# Frozen_Slimes_v2.net
KiCad netlist of a schematic drawn in EasyEDA
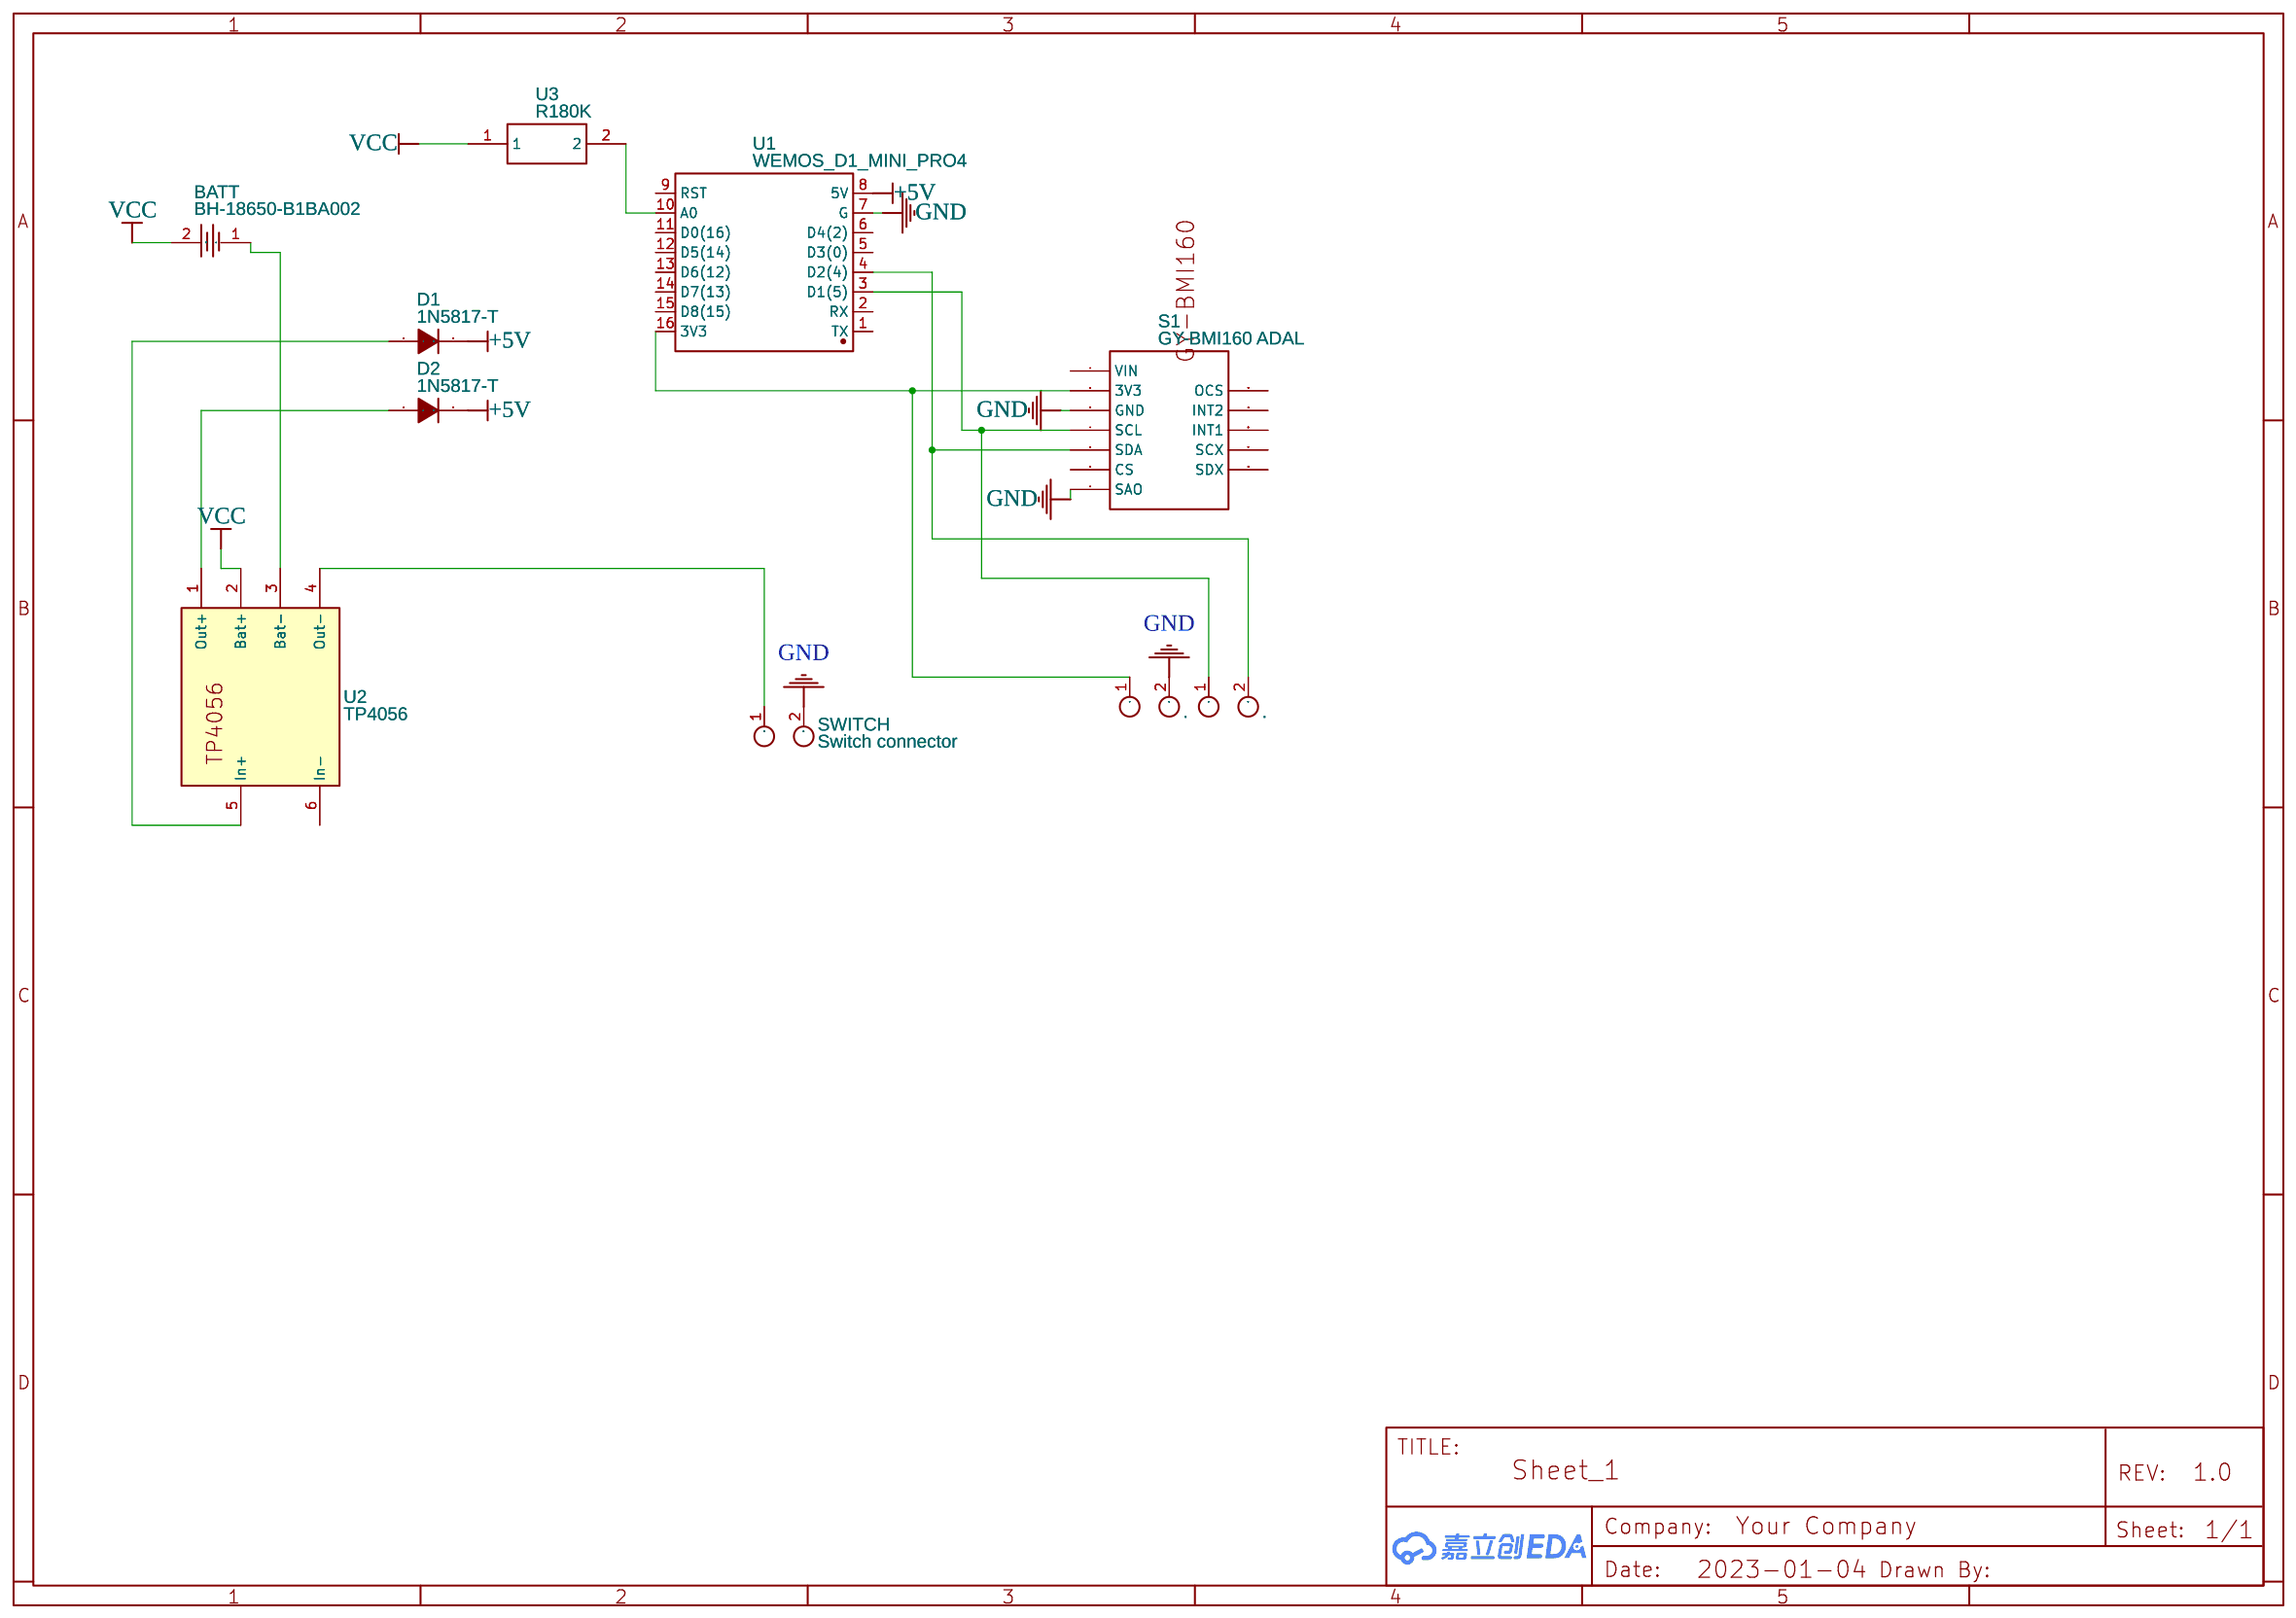
[diagram p0: schematic sheet]

(export (version "E")
  (design (tool "Eeschema 10.0.6"))
  (components
    (comp (ref "BATT")
      (value "BH-18650-B1BA002")
      (fields (field (name "BOM_Supplier Part") "C2988620"))
      (libsource (lib "") (part "BH-18650-B1BA002"))
    )
    (comp (ref "D1")
      (value "1N5817-T")
      (fields (field (name "BOM_Supplier Part") "C507852"))
      (libsource (lib "") (part "1N5817-T"))
    )
    (comp (ref "D2")
      (value "1N5817-T")
      (fields (field (name "BOM_Supplier Part") "C507852"))
      (libsource (lib "") (part "1N5817-T"))
    )
    (comp (ref "S1") (value "GY-BMI160 ADAL") (libsource (lib "") (part "GY-BMI160 ADAL")))
    (comp (ref "SWITCH") (value "Switch connector") (libsource (lib "") (part "2XSOLDER PAD_1")))
    (comp (ref "U1")
      (value "WEMOS_D1_MINI_PRO4")
      (fields
        (field (name "BOM_Manufacturer Part") "Wemos_D1_mini_Pro4")
        (field (name "BOM_Supplier Part") "C2837266")
      )
      (libsource (lib "") (part "WEMOS_D1_MINI_PRO4"))
    )
    (comp (ref "U2") (value "TP4056") (libsource (lib "") (part "TP4056")))
    (comp (ref "U3") (value "R180K") (libsource (lib "") (part "R180K")))
    (comp (ref "U6") (value ".") (libsource (lib "") (part "2XSOLDER PAD")))
    (comp (ref "U7") (value ".") (libsource (lib "") (part "2XSOLDER PAD")))
  )
  (nets
    (net (code "1") (name "+5V") (class "Default")
      (node (ref "D1") (pin "2") (pinfunction "K_2") (pintype "unspecified"))
      (node (ref "D2") (pin "2") (pinfunction "K_2") (pintype "unspecified"))
      (node (ref "U1") (pin "8") (pinfunction "5V_8") (pintype "unspecified"))
    )
    (net (code "2") (name "GND") (class "Default")
      (node (ref "S1") (pin "1") (pinfunction "SAO_1") (pintype "unspecified"))
      (node (ref "S1") (pin "5") (pinfunction "GND_5") (pintype "unspecified"))
      (node (ref "SWITCH") (pin "2") (pinfunction "2_2") (pintype "unspecified"))
      (node (ref "U1") (pin "7") (pinfunction "G_7") (pintype "unspecified"))
      (node (ref "U6") (pin "2") (pinfunction "2_2") (pintype "unspecified"))
    )
    (net (code "3") (name "Net-(D1-A)") (class "Default")
      (node (ref "D1") (pin "1") (pinfunction "A_1") (pintype "unspecified"))
      (node (ref "U2") (pin "5") (pinfunction "In+_5") (pintype "unspecified"))
    )
    (net (code "4") (name "Net-(D2-A)") (class "Default")
      (node (ref "D2") (pin "1") (pinfunction "A_1") (pintype "unspecified"))
      (node (ref "U2") (pin "1") (pinfunction "Out+_1") (pintype "unspecified"))
    )
    (net (code "5") (name "Net-(S1-3V3)") (class "Default")
      (node (ref "S1") (pin "6") (pinfunction "3V3_6") (pintype "unspecified"))
      (node (ref "U1") (pin "16") (pinfunction "3V3_16") (pintype "unspecified"))
      (node (ref "U6") (pin "1") (pinfunction "1_1") (pintype "unspecified"))
    )
    (net (code "6") (name "Net-(S1-SCL)") (class "Default")
      (node (ref "S1") (pin "4") (pinfunction "SCL_4") (pintype "unspecified"))
      (node (ref "U1") (pin "3") (pinfunction "D1(5)_3") (pintype "unspecified"))
      (node (ref "U7") (pin "1") (pinfunction "1_1") (pintype "unspecified"))
    )
    (net (code "7") (name "Net-(S1-SDA)") (class "Default")
      (node (ref "S1") (pin "3") (pinfunction "SDA_3") (pintype "unspecified"))
      (node (ref "U1") (pin "4") (pinfunction "D2(4)_4") (pintype "unspecified"))
      (node (ref "U7") (pin "2") (pinfunction "2_2") (pintype "unspecified"))
    )
    (net (code "8") (name "Net-(U1-A0)") (class "Default")
      (node (ref "U1") (pin "10") (pinfunction "A0_10") (pintype "unspecified"))
      (node (ref "U3") (pin "2") (pinfunction "2_2") (pintype "unspecified"))
    )
    (net (code "9") (name "Net-(U2-Bat-)") (class "Default")
      (node (ref "BATT") (pin "1") (pinfunction "1_1") (pintype "input"))
      (node (ref "U2") (pin "3") (pinfunction "Bat-_3") (pintype "unspecified"))
    )
    (net (code "10") (name "Net-(U2-Out-)") (class "Default")
      (node (ref "SWITCH") (pin "1") (pinfunction "1_1") (pintype "unspecified"))
      (node (ref "U2") (pin "4") (pinfunction "Out-_4") (pintype "unspecified"))
    )
    (net (code "11") (name "VCC") (class "Default")
      (node (ref "BATT") (pin "2") (pinfunction "2_2") (pintype "input"))
      (node (ref "U2") (pin "2") (pinfunction "Bat+_2") (pintype "unspecified"))
      (node (ref "U3") (pin "1") (pinfunction "1_1") (pintype "unspecified"))
    )
    (net (code "12") (name "unconnected-(S1-CS-Pad2)") (class "Default")
      (node (ref "S1") (pin "2") (pinfunction "CS_2") (pintype "unspecified"))
    )
    (net (code "13") (name "unconnected-(S1-INT1-Pad10)") (class "Default")
      (node (ref "S1") (pin "10") (pinfunction "INT1_10") (pintype "unspecified"))
    )
    (net (code "14") (name "unconnected-(S1-INT2-Pad9)") (class "Default")
      (node (ref "S1") (pin "9") (pinfunction "INT2_9") (pintype "unspecified"))
    )
    (net (code "15") (name "unconnected-(S1-OCS-Pad8)") (class "Default")
      (node (ref "S1") (pin "8") (pinfunction "OCS_8") (pintype "unspecified"))
    )
    (net (code "16") (name "unconnected-(S1-SCX-Pad11)") (class "Default")
      (node (ref "S1") (pin "11") (pinfunction "SCX_11") (pintype "unspecified"))
    )
    (net (code "17") (name "unconnected-(S1-SDX-Pad12)") (class "Default")
      (node (ref "S1") (pin "12") (pinfunction "SDX_12") (pintype "unspecified"))
    )
    (net (code "18") (name "unconnected-(S1-VIN-Pad7)") (class "Default")
      (node (ref "S1") (pin "7") (pinfunction "VIN_7") (pintype "unspecified"))
    )
    (net (code "19") (name "unconnected-(U1-D0(16)-Pad11)") (class "Default")
      (node (ref "U1") (pin "11") (pinfunction "D0(16)_11") (pintype "unspecified"))
    )
    (net (code "20") (name "unconnected-(U1-D3(0)-Pad5)") (class "Default")
      (node (ref "U1") (pin "5") (pinfunction "D3(0)_5") (pintype "unspecified"))
    )
    (net (code "21") (name "unconnected-(U1-D4(2)-Pad6)") (class "Default")
      (node (ref "U1") (pin "6") (pinfunction "D4(2)_6") (pintype "unspecified"))
    )
    (net (code "22") (name "unconnected-(U1-D5(14)-Pad12)") (class "Default")
      (node (ref "U1") (pin "12") (pinfunction "D5(14)_12") (pintype "unspecified"))
    )
    (net (code "23") (name "unconnected-(U1-D6(12)-Pad13)") (class "Default")
      (node (ref "U1") (pin "13") (pinfunction "D6(12)_13") (pintype "unspecified"))
    )
    (net (code "24") (name "unconnected-(U1-D7(13)-Pad14)") (class "Default")
      (node (ref "U1") (pin "14") (pinfunction "D7(13)_14") (pintype "unspecified"))
    )
    (net (code "25") (name "unconnected-(U1-D8(15)-Pad15)") (class "Default")
      (node (ref "U1") (pin "15") (pinfunction "D8(15)_15") (pintype "unspecified"))
    )
    (net (code "26") (name "unconnected-(U1-RST-Pad9)") (class "Default")
      (node (ref "U1") (pin "9") (pinfunction "RST_9") (pintype "unspecified"))
    )
    (net (code "27") (name "unconnected-(U1-RX-Pad2)") (class "Default")
      (node (ref "U1") (pin "2") (pinfunction "RX_2") (pintype "unspecified"))
    )
    (net (code "28") (name "unconnected-(U1-TX-Pad1)") (class "Default")
      (node (ref "U1") (pin "1") (pinfunction "TX_1") (pintype "unspecified"))
    )
    (net (code "29") (name "unconnected-(U2-In--Pad6)") (class "Default")
      (node (ref "U2") (pin "6") (pinfunction "In-_6") (pintype "unspecified"))
    )
  )
)
